# keyboard-tester.net
KiCad netlist of a schematic drawn in EAGLE
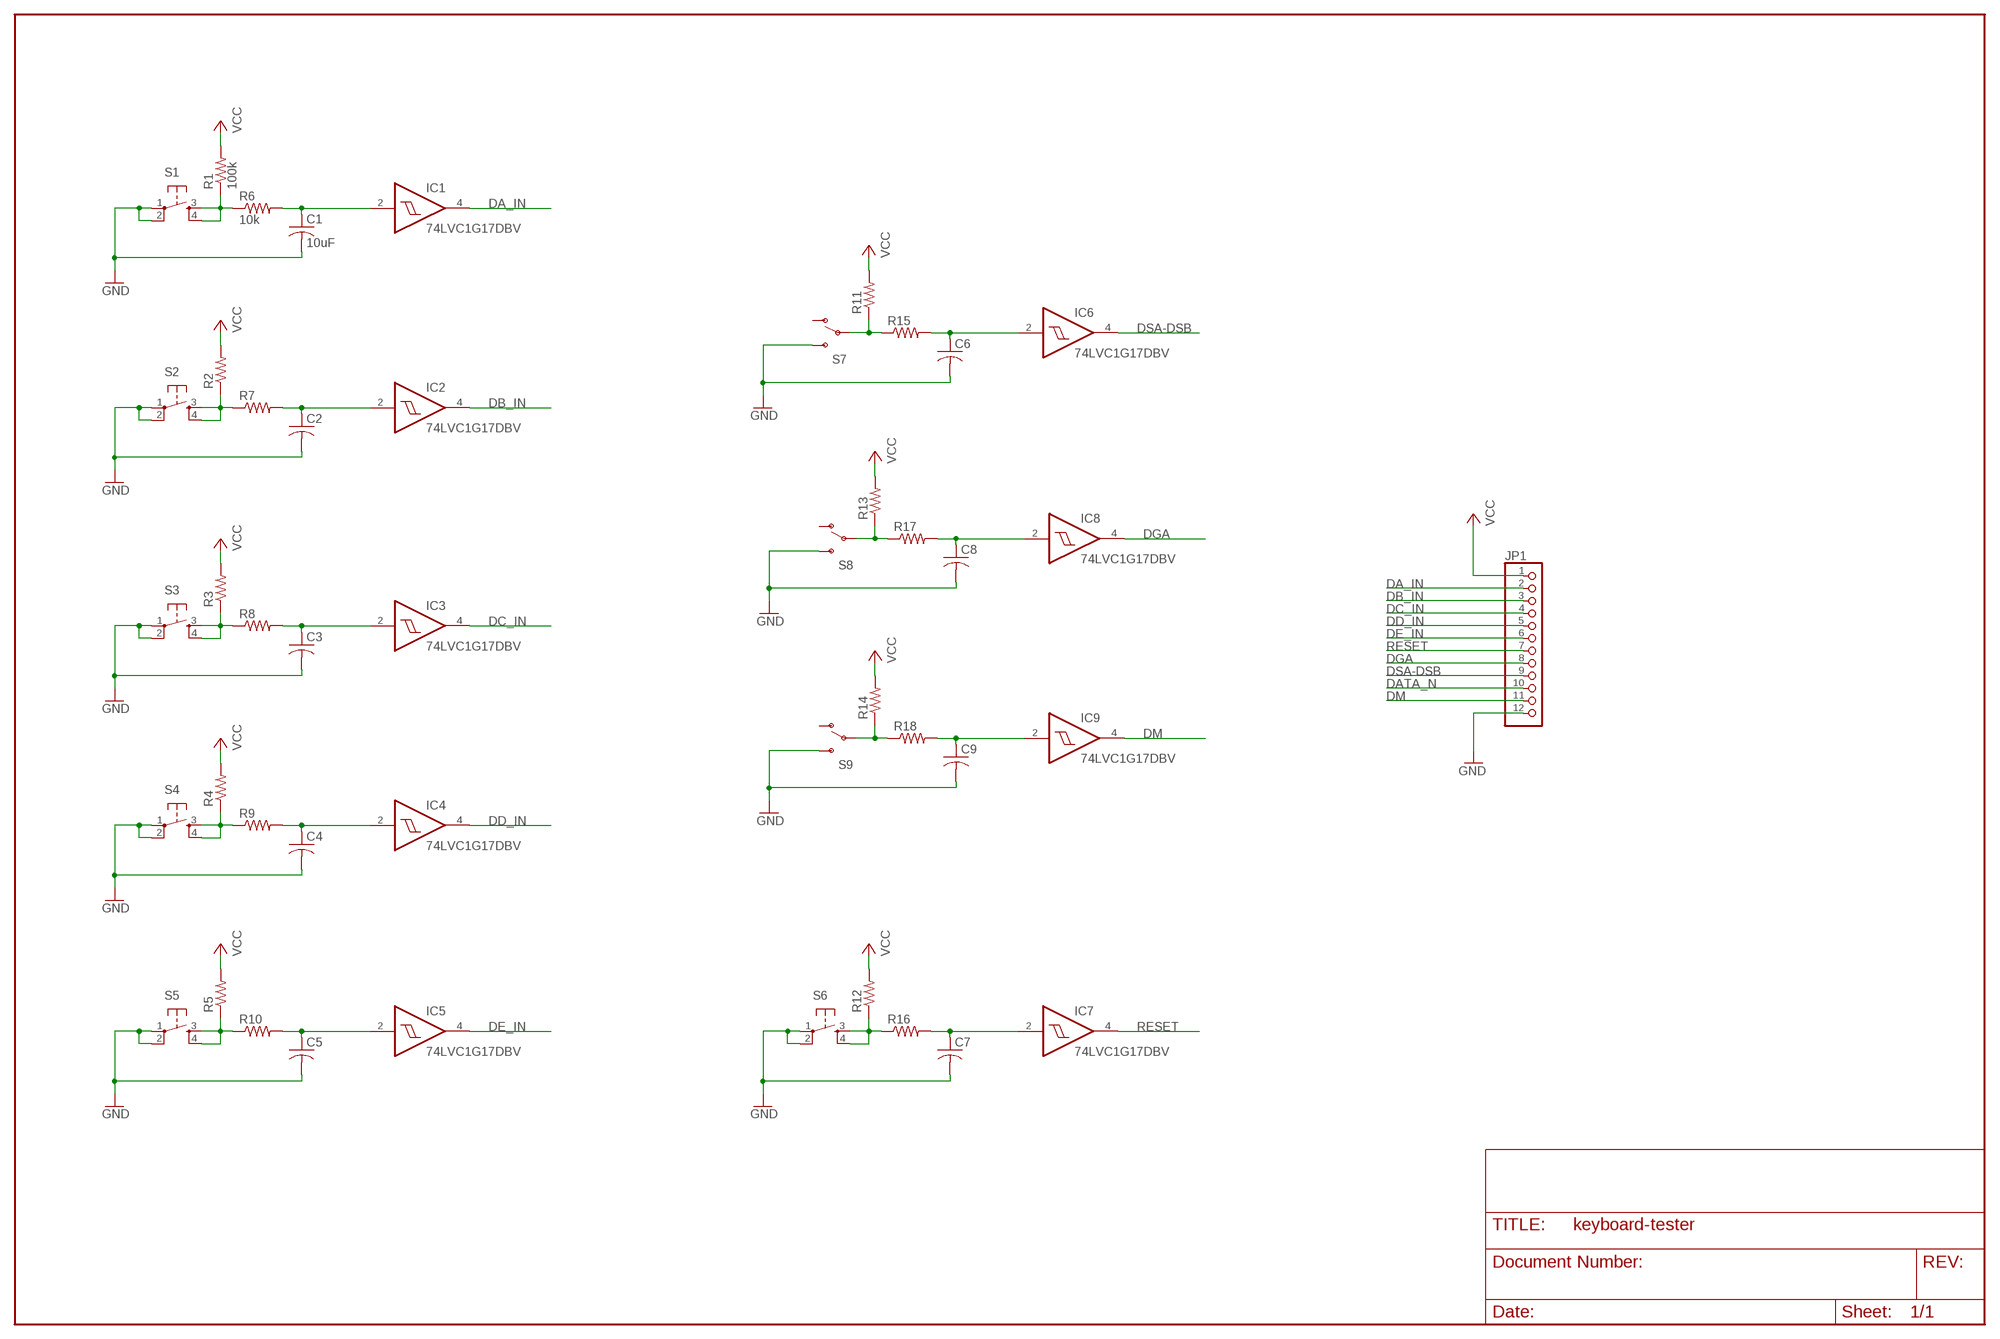
[diagram p0: schematic, sheet 1]

(export (version "E")
  (design (tool "Eeschema 10.0.6"))
  (components
    (comp (ref "C1")
      (value "10uF")
      (footprint "eagle-import:C0805")
      (libsource (lib "eagle-import") (part "C-USC0805"))
    )
    (comp (ref "C2")
      (value "C-USC0805")
      (footprint "eagle-import:C0805")
      (libsource (lib "eagle-import") (part "C-USC0805"))
    )
    (comp (ref "C3")
      (value "C-USC0805")
      (footprint "eagle-import:C0805")
      (libsource (lib "eagle-import") (part "C-USC0805"))
    )
    (comp (ref "C4")
      (value "C-USC0805")
      (footprint "eagle-import:C0805")
      (libsource (lib "eagle-import") (part "C-USC0805"))
    )
    (comp (ref "C5")
      (value "C-USC0805")
      (footprint "eagle-import:C0805")
      (libsource (lib "eagle-import") (part "C-USC0805"))
    )
    (comp (ref "C6")
      (value "C-USC0805")
      (footprint "eagle-import:C0805")
      (libsource (lib "eagle-import") (part "C-USC0805"))
    )
    (comp (ref "C7")
      (value "C-USC0805")
      (footprint "eagle-import:C0805")
      (libsource (lib "eagle-import") (part "C-USC0805"))
    )
    (comp (ref "C8")
      (value "C-USC0805")
      (footprint "eagle-import:C0805")
      (libsource (lib "eagle-import") (part "C-USC0805"))
    )
    (comp (ref "C9")
      (value "C-USC0805")
      (footprint "eagle-import:C0805")
      (libsource (lib "eagle-import") (part "C-USC0805"))
    )
    (comp (ref "IC1")
      (value "74LVC1G17DBV")
      (footprint "eagle-import:SOT23-5")
      (libsource (lib "eagle-import") (part "741G17DBVLVC"))
    )
    (comp (ref "IC2")
      (value "74LVC1G17DBV")
      (footprint "eagle-import:SOT23-5")
      (libsource (lib "eagle-import") (part "741G17DBVLVC"))
    )
    (comp (ref "IC3")
      (value "74LVC1G17DBV")
      (footprint "eagle-import:SOT23-5")
      (libsource (lib "eagle-import") (part "741G17DBVLVC"))
    )
    (comp (ref "IC4")
      (value "74LVC1G17DBV")
      (footprint "eagle-import:SOT23-5")
      (libsource (lib "eagle-import") (part "741G17DBVLVC"))
    )
    (comp (ref "IC5")
      (value "74LVC1G17DBV")
      (footprint "eagle-import:SOT23-5")
      (libsource (lib "eagle-import") (part "741G17DBVLVC"))
    )
    (comp (ref "IC6")
      (value "74LVC1G17DBV")
      (footprint "eagle-import:SOT23-5")
      (libsource (lib "eagle-import") (part "741G17DBVLVC"))
    )
    (comp (ref "IC7")
      (value "74LVC1G17DBV")
      (footprint "eagle-import:SOT23-5")
      (libsource (lib "eagle-import") (part "741G17DBVLVC"))
    )
    (comp (ref "IC8")
      (value "74LVC1G17DBV")
      (footprint "eagle-import:SOT23-5")
      (libsource (lib "eagle-import") (part "741G17DBVLVC"))
    )
    (comp (ref "IC9")
      (value "74LVC1G17DBV")
      (footprint "eagle-import:SOT23-5")
      (libsource (lib "eagle-import") (part "741G17DBVLVC"))
    )
    (comp (ref "JP1")
      (value "PINHD-1X12")
      (footprint "eagle-import:1X12")
      (libsource (lib "eagle-import") (part "PINHD-1X12"))
    )
    (comp (ref "R1")
      (value "100k")
      (footprint "eagle-import:R0805")
      (libsource (lib "eagle-import") (part "R-US_R0805"))
    )
    (comp (ref "R2")
      (value "R-US_R0805")
      (footprint "eagle-import:R0805")
      (libsource (lib "eagle-import") (part "R-US_R0805"))
    )
    (comp (ref "R3")
      (value "R-US_R0805")
      (footprint "eagle-import:R0805")
      (libsource (lib "eagle-import") (part "R-US_R0805"))
    )
    (comp (ref "R4")
      (value "R-US_R0805")
      (footprint "eagle-import:R0805")
      (libsource (lib "eagle-import") (part "R-US_R0805"))
    )
    (comp (ref "R5")
      (value "R-US_R0805")
      (footprint "eagle-import:R0805")
      (libsource (lib "eagle-import") (part "R-US_R0805"))
    )
    (comp (ref "R6")
      (value "10k")
      (footprint "eagle-import:R0805")
      (libsource (lib "eagle-import") (part "R-US_R0805"))
    )
    (comp (ref "R7")
      (value "R-US_R0805")
      (footprint "eagle-import:R0805")
      (libsource (lib "eagle-import") (part "R-US_R0805"))
    )
    (comp (ref "R8")
      (value "R-US_R0805")
      (footprint "eagle-import:R0805")
      (libsource (lib "eagle-import") (part "R-US_R0805"))
    )
    (comp (ref "R9")
      (value "R-US_R0805")
      (footprint "eagle-import:R0805")
      (libsource (lib "eagle-import") (part "R-US_R0805"))
    )
    (comp (ref "R10")
      (value "R-US_R0805")
      (footprint "eagle-import:R0805")
      (libsource (lib "eagle-import") (part "R-US_R0805"))
    )
    (comp (ref "R11")
      (value "R-US_R0805")
      (footprint "eagle-import:R0805")
      (libsource (lib "eagle-import") (part "R-US_R0805"))
    )
    (comp (ref "R12")
      (value "R-US_R0805")
      (footprint "eagle-import:R0805")
      (libsource (lib "eagle-import") (part "R-US_R0805"))
    )
    (comp (ref "R13")
      (value "R-US_R0805")
      (footprint "eagle-import:R0805")
      (libsource (lib "eagle-import") (part "R-US_R0805"))
    )
    (comp (ref "R14")
      (value "R-US_R0805")
      (footprint "eagle-import:R0805")
      (libsource (lib "eagle-import") (part "R-US_R0805"))
    )
    (comp (ref "R15")
      (value "R-US_R0805")
      (footprint "eagle-import:R0805")
      (libsource (lib "eagle-import") (part "R-US_R0805"))
    )
    (comp (ref "R16")
      (value "R-US_R0805")
      (footprint "eagle-import:R0805")
      (libsource (lib "eagle-import") (part "R-US_R0805"))
    )
    (comp (ref "R17")
      (value "R-US_R0805")
      (footprint "eagle-import:R0805")
      (libsource (lib "eagle-import") (part "R-US_R0805"))
    )
    (comp (ref "R18")
      (value "R-US_R0805")
      (footprint "eagle-import:R0805")
      (libsource (lib "eagle-import") (part "R-US_R0805"))
    )
    (comp (ref "S1")
      (value "TAC_SWITCHPTH")
      (footprint "eagle-import:TACTILE-PTH")
      (libsource (lib "eagle-import") (part "TAC_SWITCHPTH"))
    )
    (comp (ref "S2")
      (value "TAC_SWITCHPTH")
      (footprint "eagle-import:TACTILE-PTH")
      (libsource (lib "eagle-import") (part "TAC_SWITCHPTH"))
    )
    (comp (ref "S3")
      (value "TAC_SWITCHPTH")
      (footprint "eagle-import:TACTILE-PTH")
      (libsource (lib "eagle-import") (part "TAC_SWITCHPTH"))
    )
    (comp (ref "S4")
      (value "TAC_SWITCHPTH")
      (footprint "eagle-import:TACTILE-PTH")
      (libsource (lib "eagle-import") (part "TAC_SWITCHPTH"))
    )
    (comp (ref "S5")
      (value "TAC_SWITCHPTH")
      (footprint "eagle-import:TACTILE-PTH")
      (libsource (lib "eagle-import") (part "TAC_SWITCHPTH"))
    )
    (comp (ref "S6")
      (value "TAC_SWITCHPTH")
      (footprint "eagle-import:TACTILE-PTH")
      (libsource (lib "eagle-import") (part "TAC_SWITCHPTH"))
    )
    (comp (ref "S7")
      (value "SWITCH-SPDTPTH")
      (footprint "eagle-import:SWITCH-SPDT")
      (libsource (lib "eagle-import") (part "SWITCH-SPDTPTH"))
    )
    (comp (ref "S8")
      (value "SWITCH-SPDTPTH")
      (footprint "eagle-import:SWITCH-SPDT")
      (libsource (lib "eagle-import") (part "SWITCH-SPDTPTH"))
    )
    (comp (ref "S9")
      (value "SWITCH-SPDTPTH")
      (footprint "eagle-import:SWITCH-SPDT")
      (libsource (lib "eagle-import") (part "SWITCH-SPDTPTH"))
    )
  )
  (nets
    (net (code "1") (name "/DATA_N") (class "Default")
      (node (ref "JP1") (pin "10") (pinfunction "10_10") (pintype "passive"))
    )
    (net (code "2") (name "/DA_IN") (class "Default")
      (node (ref "IC1") (pin "4") (pinfunction "O_4") (pintype "output"))
      (node (ref "JP1") (pin "2") (pinfunction "2_2") (pintype "passive"))
    )
    (net (code "3") (name "/DB_IN") (class "Default")
      (node (ref "IC2") (pin "4") (pinfunction "O_4") (pintype "output"))
      (node (ref "JP1") (pin "3") (pinfunction "3_3") (pintype "passive"))
    )
    (net (code "4") (name "/DC_IN") (class "Default")
      (node (ref "IC3") (pin "4") (pinfunction "O_4") (pintype "output"))
      (node (ref "JP1") (pin "4") (pinfunction "4_4") (pintype "passive"))
    )
    (net (code "5") (name "/DD_IN") (class "Default")
      (node (ref "IC4") (pin "4") (pinfunction "O_4") (pintype "output"))
      (node (ref "JP1") (pin "5") (pinfunction "5_5") (pintype "passive"))
    )
    (net (code "6") (name "/DE_IN") (class "Default")
      (node (ref "IC5") (pin "4") (pinfunction "O_4") (pintype "output"))
      (node (ref "JP1") (pin "6") (pinfunction "6_6") (pintype "passive"))
    )
    (net (code "7") (name "/DGA") (class "Default")
      (node (ref "IC8") (pin "4") (pinfunction "O_4") (pintype "output"))
      (node (ref "JP1") (pin "8") (pinfunction "8_8") (pintype "passive"))
    )
    (net (code "8") (name "/DM") (class "Default")
      (node (ref "IC9") (pin "4") (pinfunction "O_4") (pintype "output"))
      (node (ref "JP1") (pin "11") (pinfunction "11_11") (pintype "passive"))
    )
    (net (code "9") (name "/DSA-DSB") (class "Default")
      (node (ref "IC6") (pin "4") (pinfunction "O_4") (pintype "output"))
      (node (ref "JP1") (pin "9") (pinfunction "9_9") (pintype "passive"))
    )
    (net (code "10") (name "/RESET") (class "Default")
      (node (ref "IC7") (pin "4") (pinfunction "O_4") (pintype "output"))
      (node (ref "JP1") (pin "7") (pinfunction "7_7") (pintype "passive"))
    )
    (net (code "11") (name "GND") (class "Default")
      (node (ref "C1") (pin "2") (pinfunction "2_2") (pintype "passive"))
      (node (ref "C2") (pin "2") (pinfunction "2_2") (pintype "passive"))
      (node (ref "C3") (pin "2") (pinfunction "2_2") (pintype "passive"))
      (node (ref "C4") (pin "2") (pinfunction "2_2") (pintype "passive"))
      (node (ref "C5") (pin "2") (pinfunction "2_2") (pintype "passive"))
      (node (ref "C6") (pin "2") (pinfunction "2_2") (pintype "passive"))
      (node (ref "C7") (pin "2") (pinfunction "2_2") (pintype "passive"))
      (node (ref "C8") (pin "2") (pinfunction "2_2") (pintype "passive"))
      (node (ref "C9") (pin "2") (pinfunction "2_2") (pintype "passive"))
      (node (ref "JP1") (pin "12") (pinfunction "12_12") (pintype "passive"))
      (node (ref "S1") (pin "1") (pinfunction "1_1") (pintype "passive"))
      (node (ref "S1") (pin "2") (pinfunction "2_2") (pintype "passive"))
      (node (ref "S2") (pin "1") (pinfunction "1_1") (pintype "passive"))
      (node (ref "S2") (pin "2") (pinfunction "2_2") (pintype "passive"))
      (node (ref "S3") (pin "1") (pinfunction "1_1") (pintype "passive"))
      (node (ref "S3") (pin "2") (pinfunction "2_2") (pintype "passive"))
      (node (ref "S4") (pin "1") (pinfunction "1_1") (pintype "passive"))
      (node (ref "S4") (pin "2") (pinfunction "2_2") (pintype "passive"))
      (node (ref "S5") (pin "1") (pinfunction "1_1") (pintype "passive"))
      (node (ref "S5") (pin "2") (pinfunction "2_2") (pintype "passive"))
      (node (ref "S6") (pin "1") (pinfunction "1_1") (pintype "passive"))
      (node (ref "S6") (pin "2") (pinfunction "2_2") (pintype "passive"))
      (node (ref "S7") (pin "3") (pinfunction "S_3") (pintype "passive"))
      (node (ref "S8") (pin "3") (pinfunction "S_3") (pintype "passive"))
      (node (ref "S9") (pin "3") (pinfunction "S_3") (pintype "passive"))
    )
    (net (code "12") (name "Net-(IC1A-I)") (class "Default")
      (node (ref "C1") (pin "1") (pinfunction "1_1") (pintype "passive"))
      (node (ref "IC1") (pin "2") (pinfunction "I_2") (pintype "input"))
      (node (ref "R6") (pin "2") (pinfunction "2_2") (pintype "passive"))
    )
    (net (code "13") (name "Net-(IC2A-I)") (class "Default")
      (node (ref "C2") (pin "1") (pinfunction "1_1") (pintype "passive"))
      (node (ref "IC2") (pin "2") (pinfunction "I_2") (pintype "input"))
      (node (ref "R7") (pin "2") (pinfunction "2_2") (pintype "passive"))
    )
    (net (code "14") (name "Net-(IC3A-I)") (class "Default")
      (node (ref "C3") (pin "1") (pinfunction "1_1") (pintype "passive"))
      (node (ref "IC3") (pin "2") (pinfunction "I_2") (pintype "input"))
      (node (ref "R8") (pin "2") (pinfunction "2_2") (pintype "passive"))
    )
    (net (code "15") (name "Net-(IC4A-I)") (class "Default")
      (node (ref "C4") (pin "1") (pinfunction "1_1") (pintype "passive"))
      (node (ref "IC4") (pin "2") (pinfunction "I_2") (pintype "input"))
      (node (ref "R9") (pin "2") (pinfunction "2_2") (pintype "passive"))
    )
    (net (code "16") (name "Net-(IC5A-I)") (class "Default")
      (node (ref "C5") (pin "1") (pinfunction "1_1") (pintype "passive"))
      (node (ref "IC5") (pin "2") (pinfunction "I_2") (pintype "input"))
      (node (ref "R10") (pin "2") (pinfunction "2_2") (pintype "passive"))
    )
    (net (code "17") (name "Net-(IC6A-I)") (class "Default")
      (node (ref "C6") (pin "1") (pinfunction "1_1") (pintype "passive"))
      (node (ref "IC6") (pin "2") (pinfunction "I_2") (pintype "input"))
      (node (ref "R15") (pin "2") (pinfunction "2_2") (pintype "passive"))
    )
    (net (code "18") (name "Net-(IC7A-I)") (class "Default")
      (node (ref "C7") (pin "1") (pinfunction "1_1") (pintype "passive"))
      (node (ref "IC7") (pin "2") (pinfunction "I_2") (pintype "input"))
      (node (ref "R16") (pin "2") (pinfunction "2_2") (pintype "passive"))
    )
    (net (code "19") (name "Net-(IC8A-I)") (class "Default")
      (node (ref "C8") (pin "1") (pinfunction "1_1") (pintype "passive"))
      (node (ref "IC8") (pin "2") (pinfunction "I_2") (pintype "input"))
      (node (ref "R17") (pin "2") (pinfunction "2_2") (pintype "passive"))
    )
    (net (code "20") (name "Net-(IC9A-I)") (class "Default")
      (node (ref "C9") (pin "1") (pinfunction "1_1") (pintype "passive"))
      (node (ref "IC9") (pin "2") (pinfunction "I_2") (pintype "input"))
      (node (ref "R18") (pin "2") (pinfunction "2_2") (pintype "passive"))
    )
    (net (code "21") (name "Net-(R1-Pad1)") (class "Default")
      (node (ref "R1") (pin "1") (pinfunction "1_1") (pintype "passive"))
      (node (ref "R6") (pin "1") (pinfunction "1_1") (pintype "passive"))
      (node (ref "S1") (pin "3") (pinfunction "3_3") (pintype "passive"))
      (node (ref "S1") (pin "4") (pinfunction "4_4") (pintype "passive"))
    )
    (net (code "22") (name "Net-(R2-Pad1)") (class "Default")
      (node (ref "R2") (pin "1") (pinfunction "1_1") (pintype "passive"))
      (node (ref "R7") (pin "1") (pinfunction "1_1") (pintype "passive"))
      (node (ref "S2") (pin "3") (pinfunction "3_3") (pintype "passive"))
      (node (ref "S2") (pin "4") (pinfunction "4_4") (pintype "passive"))
    )
    (net (code "23") (name "Net-(R3-Pad1)") (class "Default")
      (node (ref "R3") (pin "1") (pinfunction "1_1") (pintype "passive"))
      (node (ref "R8") (pin "1") (pinfunction "1_1") (pintype "passive"))
      (node (ref "S3") (pin "3") (pinfunction "3_3") (pintype "passive"))
      (node (ref "S3") (pin "4") (pinfunction "4_4") (pintype "passive"))
    )
    (net (code "24") (name "Net-(R4-Pad1)") (class "Default")
      (node (ref "R4") (pin "1") (pinfunction "1_1") (pintype "passive"))
      (node (ref "R9") (pin "1") (pinfunction "1_1") (pintype "passive"))
      (node (ref "S4") (pin "3") (pinfunction "3_3") (pintype "passive"))
      (node (ref "S4") (pin "4") (pinfunction "4_4") (pintype "passive"))
    )
    (net (code "25") (name "Net-(R10-Pad1)") (class "Default")
      (node (ref "R10") (pin "1") (pinfunction "1_1") (pintype "passive"))
      (node (ref "R5") (pin "1") (pinfunction "1_1") (pintype "passive"))
      (node (ref "S5") (pin "3") (pinfunction "3_3") (pintype "passive"))
      (node (ref "S5") (pin "4") (pinfunction "4_4") (pintype "passive"))
    )
    (net (code "26") (name "Net-(R12-Pad1)") (class "Default")
      (node (ref "R12") (pin "1") (pinfunction "1_1") (pintype "passive"))
      (node (ref "R16") (pin "1") (pinfunction "1_1") (pintype "passive"))
      (node (ref "S6") (pin "3") (pinfunction "3_3") (pintype "passive"))
      (node (ref "S6") (pin "4") (pinfunction "4_4") (pintype "passive"))
    )
    (net (code "27") (name "Net-(S7-P)") (class "Default")
      (node (ref "R11") (pin "1") (pinfunction "1_1") (pintype "passive"))
      (node (ref "R15") (pin "1") (pinfunction "1_1") (pintype "passive"))
      (node (ref "S7") (pin "2") (pinfunction "P_2") (pintype "passive"))
    )
    (net (code "28") (name "Net-(S8-P)") (class "Default")
      (node (ref "R13") (pin "1") (pinfunction "1_1") (pintype "passive"))
      (node (ref "R17") (pin "1") (pinfunction "1_1") (pintype "passive"))
      (node (ref "S8") (pin "2") (pinfunction "P_2") (pintype "passive"))
    )
    (net (code "29") (name "Net-(S9-P)") (class "Default")
      (node (ref "R14") (pin "1") (pinfunction "1_1") (pintype "passive"))
      (node (ref "R18") (pin "1") (pinfunction "1_1") (pintype "passive"))
      (node (ref "S9") (pin "2") (pinfunction "P_2") (pintype "passive"))
    )
    (net (code "30") (name "VCC") (class "Default")
      (node (ref "JP1") (pin "1") (pinfunction "1_1") (pintype "passive"))
      (node (ref "R1") (pin "2") (pinfunction "2_2") (pintype "passive"))
      (node (ref "R11") (pin "2") (pinfunction "2_2") (pintype "passive"))
      (node (ref "R12") (pin "2") (pinfunction "2_2") (pintype "passive"))
      (node (ref "R13") (pin "2") (pinfunction "2_2") (pintype "passive"))
      (node (ref "R14") (pin "2") (pinfunction "2_2") (pintype "passive"))
      (node (ref "R2") (pin "2") (pinfunction "2_2") (pintype "passive"))
      (node (ref "R3") (pin "2") (pinfunction "2_2") (pintype "passive"))
      (node (ref "R4") (pin "2") (pinfunction "2_2") (pintype "passive"))
      (node (ref "R5") (pin "2") (pinfunction "2_2") (pintype "passive"))
    )
    (net (code "31") (name "unconnected-(S7-O-Pad1)") (class "Default")
      (node (ref "S7") (pin "1") (pinfunction "O_1") (pintype "passive"))
    )
    (net (code "32") (name "unconnected-(S8-O-Pad1)") (class "Default")
      (node (ref "S8") (pin "1") (pinfunction "O_1") (pintype "passive"))
    )
    (net (code "33") (name "unconnected-(S9-O-Pad1)") (class "Default")
      (node (ref "S9") (pin "1") (pinfunction "O_1") (pintype "passive"))
    )
  )
)
